# 9doFORK.net
KiCad netlist of a schematic drawn in EAGLE
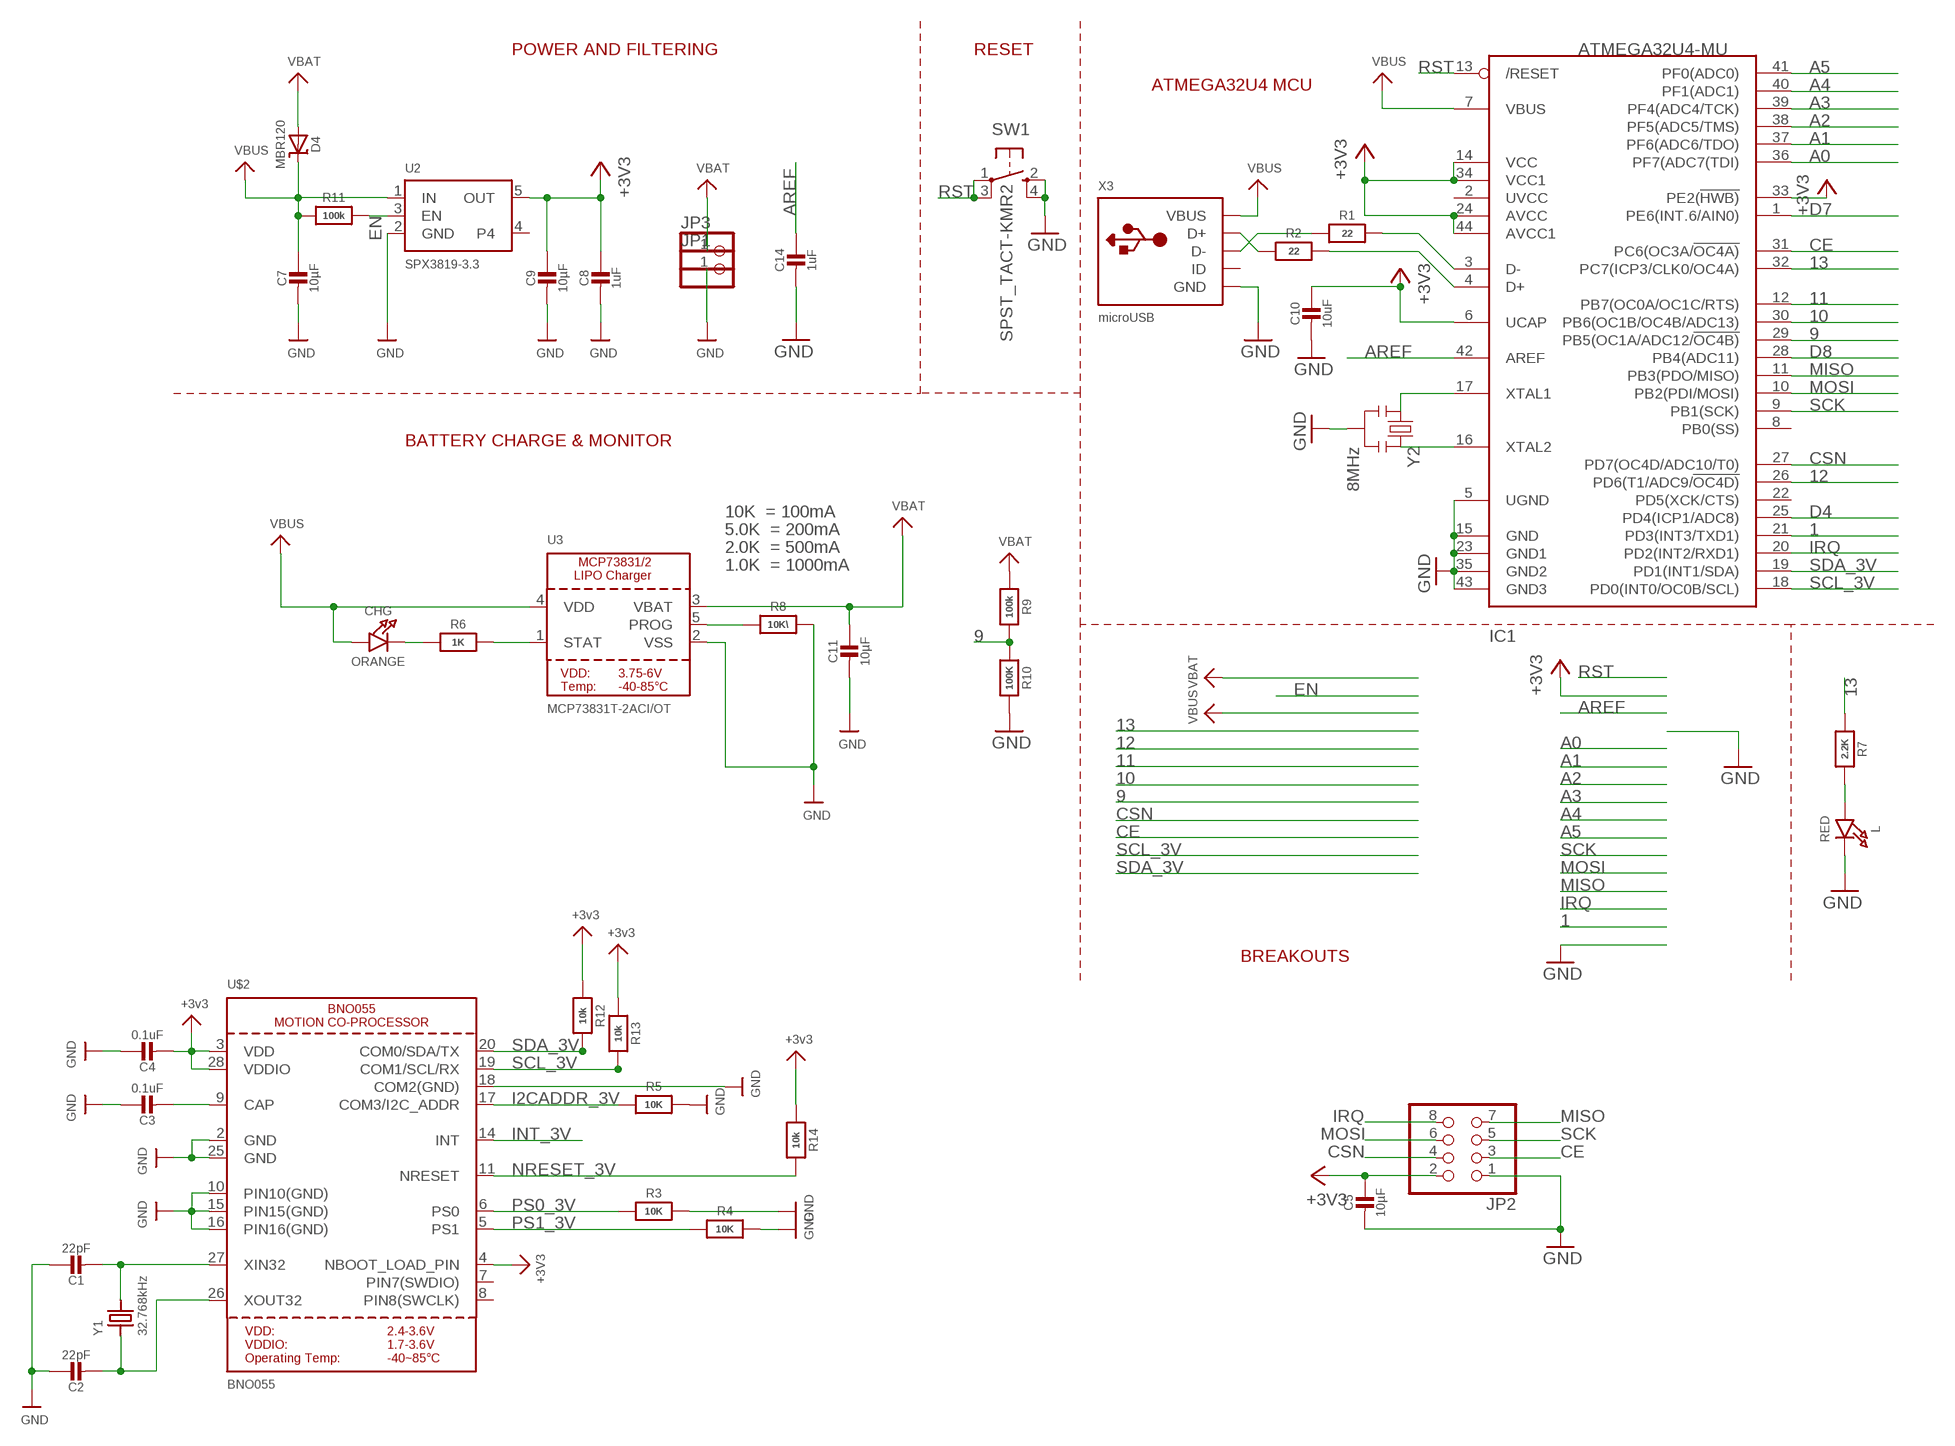
[diagram p0: schematic, sheet 1]

(export (version "E")
  (design (tool "Eeschema 10.0.6"))
  (components
    (comp (ref "C1")
      (value "22pF")
      (footprint "eagle-import:0805-NO")
      (libsource (lib "eagle-import") (part "CAP_CERAMIC0805-NOOUTLINE"))
    )
    (comp (ref "C2")
      (value "22pF")
      (footprint "eagle-import:0805-NO")
      (libsource (lib "eagle-import") (part "CAP_CERAMIC0805-NOOUTLINE"))
    )
    (comp (ref "C3")
      (value "0.1uF")
      (footprint "eagle-import:0805-NO")
      (libsource (lib "eagle-import") (part "CAP_CERAMIC0805-NOOUTLINE"))
    )
    (comp (ref "C4")
      (value "0.1uF")
      (footprint "eagle-import:0805_10MGAP")
      (libsource (lib "eagle-import") (part "CAP_CERAMIC0805_10MGAP"))
    )
    (comp (ref "C5")
      (value "10µF")
      (footprint "eagle-import:0805-NO")
      (libsource (lib "eagle-import") (part "CAP_CERAMIC0805-NOOUTLINE"))
    )
    (comp (ref "C7")
      (value "10µF")
      (footprint "eagle-import:0805-NO")
      (libsource (lib "eagle-import") (part "CAP_CERAMIC0805-NOOUTLINE"))
    )
    (comp (ref "C8")
      (value "1uF")
      (footprint "eagle-import:0603-NO")
      (libsource (lib "eagle-import") (part "CAP_CERAMIC0603_NO"))
    )
    (comp (ref "C9")
      (value "10µF")
      (footprint "eagle-import:0805-NO")
      (libsource (lib "eagle-import") (part "CAP_CERAMIC0805-NOOUTLINE"))
    )
    (comp (ref "C10")
      (value "10uF")
      (footprint "eagle-import:0805-NO")
      (libsource (lib "eagle-import") (part "CAP_CERAMIC0805-NOOUTLINE"))
    )
    (comp (ref "C11")
      (value "10µF")
      (footprint "eagle-import:0805-NO")
      (libsource (lib "eagle-import") (part "CAP_CERAMIC0805-NOOUTLINE"))
    )
    (comp (ref "C14")
      (value "1uF")
      (footprint "eagle-import:0603-NO")
      (libsource (lib "eagle-import") (part "CAP_CERAMIC0603_NO"))
    )
    (comp (ref "CHG")
      (value "ORANGE")
      (footprint "eagle-import:CHIPLED_0805_NOOUTLINE")
      (libsource (lib "eagle-import") (part "LED0805_NOOUTLINE"))
    )
    (comp (ref "D4")
      (value "MBR120")
      (footprint "eagle-import:SOD-123")
      (libsource (lib "eagle-import") (part "DIODE-SCHOTTKYSOD-123"))
    )
    (comp (ref "IC1")
      (value "ATMEGA32U4-MU")
      (footprint "eagle-import:TQFN44_7MM")
      (libsource (lib "eagle-import") (part "ATMEGA32U4-MU"))
    )
    (comp (ref "JP1")
      (value "PINHD-1X1")
      (footprint "eagle-import:1X01")
      (libsource (lib "eagle-import") (part "PINHD-1X1"))
    )
    (comp (ref "JP2")
      (value "PINHD-2X4")
      (footprint "eagle-import:2X04")
      (libsource (lib "eagle-import") (part "PINHD-2X4"))
    )
    (comp (ref "JP3")
      (value "PINHD-1X1")
      (footprint "eagle-import:1X01")
      (libsource (lib "eagle-import") (part "PINHD-1X1"))
    )
    (comp (ref "L")
      (value "RED")
      (footprint "eagle-import:CHIPLED_0805_NOOUTLINE")
      (libsource (lib "eagle-import") (part "LED0805_NOOUTLINE"))
    )
    (comp (ref "R1")
      (value "22")
      (footprint "eagle-import:0603-NO")
      (libsource (lib "eagle-import") (part "RESISTOR_0603_NOOUT"))
    )
    (comp (ref "R2")
      (value "22")
      (footprint "eagle-import:0603-NO")
      (libsource (lib "eagle-import") (part "RESISTOR_0603_NOOUT"))
    )
    (comp (ref "R3")
      (value "10K")
      (footprint "eagle-import:0805-NO")
      (libsource (lib "eagle-import") (part "RESISTOR0805_NOOUTLINE"))
    )
    (comp (ref "R4")
      (value "10K")
      (footprint "eagle-import:0805-NO")
      (libsource (lib "eagle-import") (part "RESISTOR0805_NOOUTLINE"))
    )
    (comp (ref "R5")
      (value "10K")
      (footprint "eagle-import:0805-NO")
      (libsource (lib "eagle-import") (part "RESISTOR0805_NOOUTLINE"))
    )
    (comp (ref "R6")
      (value "1K")
      (footprint "eagle-import:0603-NO")
      (libsource (lib "eagle-import") (part "RESISTOR_0603_NOOUT"))
    )
    (comp (ref "R7")
      (value "2.2K")
      (footprint "eagle-import:0603-NO")
      (libsource (lib "eagle-import") (part "RESISTOR_0603_NOOUT"))
    )
    (comp (ref "R8")
      (value "10K\\")
      (footprint "eagle-import:0603-NO")
      (libsource (lib "eagle-import") (part "RESISTOR_0603_NOOUT"))
    )
    (comp (ref "R9")
      (value "100k")
      (footprint "eagle-import:0603-NO")
      (libsource (lib "eagle-import") (part "RESISTOR_0603_NOOUT"))
    )
    (comp (ref "R10")
      (value "100K")
      (footprint "eagle-import:_0603MP")
      (libsource (lib "eagle-import") (part "RESISTOR_0603MP"))
    )
    (comp (ref "R11")
      (value "100k")
      (footprint "eagle-import:0603-NO")
      (libsource (lib "eagle-import") (part "RESISTOR_0603_NOOUT"))
    )
    (comp (ref "R12")
      (value "10k")
      (footprint "eagle-import:0603-NO")
      (libsource (lib "eagle-import") (part "RESISTOR_0603_NOOUT"))
    )
    (comp (ref "R13")
      (value "10k")
      (footprint "eagle-import:0603-NO")
      (libsource (lib "eagle-import") (part "RESISTOR_0603_NOOUT"))
    )
    (comp (ref "R14")
      (value "10k")
      (footprint "eagle-import:0603-NO")
      (libsource (lib "eagle-import") (part "RESISTOR_0603_NOOUT"))
    )
    (comp (ref "SW1")
      (value "SPST_TACT-KMR2")
      (footprint "eagle-import:KMR2")
      (libsource (lib "eagle-import") (part "SPST_TACT-KMR2"))
    )
    (comp (ref "U$2")
      (value "BNO055")
      (footprint "eagle-import:BNO055")
      (libsource (lib "eagle-import") (part "BNO055"))
    )
    (comp (ref "U2")
      (value "SPX3819-3.3")
      (footprint "eagle-import:SOT23-5")
      (libsource (lib "eagle-import") (part "VREG_SOT23-5"))
    )
    (comp (ref "U3")
      (value "MCP73831T-2ACI/OT")
      (footprint "eagle-import:SOT23-5")
      (libsource (lib "eagle-import") (part "MCP73831/2"))
    )
    (comp (ref "X3")
      (value "microUSB")
      (footprint "eagle-import:4UCONN_20329_V2")
      (libsource (lib "eagle-import") (part "USB_MICRO_20329_V2"))
    )
    (comp (ref "Y1")
      (value "32.768kHz")
      (footprint "eagle-import:CRYSTAL_8X3.8")
      (libsource (lib "eagle-import") (part "CRYSTAL8.0X3.8"))
    )
    (comp (ref "Y2")
      (value "8MHz")
      (footprint "eagle-import:RESONATOR-SMD")
      (libsource (lib "eagle-import") (part "RESONATORSMD"))
    )
  )
  (nets
    (net (code "1") (name "+3V3") (class "Default")
      (node (ref "C10") (pin "1") (pinfunction "1_1") (pintype "passive"))
      (node (ref "C4") (pin "2") (pinfunction "2_2") (pintype "passive"))
      (node (ref "C5") (pin "1") (pinfunction "1_1") (pintype "passive"))
      (node (ref "C8") (pin "1") (pinfunction "1_1") (pintype "passive"))
      (node (ref "C9") (pin "1") (pinfunction "1_1") (pintype "passive"))
      (node (ref "IC1") (pin "14") (pinfunction "VCC_14") (pintype "bidirectional"))
      (node (ref "IC1") (pin "24") (pinfunction "AVCC_24") (pintype "bidirectional"))
      (node (ref "IC1") (pin "33") (pinfunction "PE2(~{HWB})_33") (pintype "bidirectional"))
      (node (ref "IC1") (pin "34") (pinfunction "VCC1_34") (pintype "bidirectional"))
      (node (ref "IC1") (pin "44") (pinfunction "AVCC1_44") (pintype "bidirectional"))
      (node (ref "IC1") (pin "6") (pinfunction "UCAP_6") (pintype "bidirectional"))
      (node (ref "JP2") (pin "2") (pinfunction "2_2") (pintype "passive"))
      (node (ref "R12") (pin "1") (pinfunction "1_1") (pintype "passive"))
      (node (ref "R13") (pin "1") (pinfunction "1_1") (pintype "passive"))
      (node (ref "R14") (pin "1") (pinfunction "1_1") (pintype "passive"))
      (node (ref "U$2") (pin "28") (pinfunction "VDDIO_28") (pintype "power_in"))
      (node (ref "U$2") (pin "3") (pinfunction "VDD_3") (pintype "power_in"))
      (node (ref "U$2") (pin "4") (pinfunction "NBOOT_LOAD_PIN_4") (pintype "bidirectional"))
      (node (ref "U2") (pin "5") (pinfunction "OUT_5") (pintype "power_in"))
    )
    (net (code "2") (name "/1") (class "Default")
      (node (ref "IC1") (pin "21") (pinfunction "PD3(INT3/TXD1)_21") (pintype "bidirectional"))
    )
    (net (code "3") (name "/9") (class "Default")
      (node (ref "IC1") (pin "29") (pinfunction "PB5(OC1A/ADC12/~{OC4B})_29") (pintype "bidirectional"))
      (node (ref "R10") (pin "1") (pinfunction "1_1") (pintype "passive"))
      (node (ref "R9") (pin "2") (pinfunction "2_2") (pintype "passive"))
    )
    (net (code "4") (name "/10") (class "Default")
      (node (ref "IC1") (pin "30") (pinfunction "PB6(OC1B/OC4B/ADC13)_30") (pintype "bidirectional"))
    )
    (net (code "5") (name "/11") (class "Default")
      (node (ref "IC1") (pin "12") (pinfunction "PB7(OC0A/OC1C/RTS)_12") (pintype "bidirectional"))
    )
    (net (code "6") (name "/12") (class "Default")
      (node (ref "IC1") (pin "26") (pinfunction "PD6(T1/ADC9/~{OC4D})_26") (pintype "bidirectional"))
    )
    (net (code "7") (name "/13") (class "Default")
      (node (ref "IC1") (pin "32") (pinfunction "PC7(ICP3/CLK0/OC4A)_32") (pintype "bidirectional"))
      (node (ref "R7") (pin "1") (pinfunction "1_1") (pintype "passive"))
    )
    (net (code "8") (name "/A0") (class "Default")
      (node (ref "IC1") (pin "36") (pinfunction "PF7(ADC7(TDI)_36") (pintype "bidirectional"))
    )
    (net (code "9") (name "/A1") (class "Default")
      (node (ref "IC1") (pin "37") (pinfunction "PF6(ADC6/TDO)_37") (pintype "bidirectional"))
    )
    (net (code "10") (name "/A2") (class "Default")
      (node (ref "IC1") (pin "38") (pinfunction "PF5(ADC5/TMS)_38") (pintype "bidirectional"))
    )
    (net (code "11") (name "/A3") (class "Default")
      (node (ref "IC1") (pin "39") (pinfunction "PF4(ADC4/TCK)_39") (pintype "bidirectional"))
    )
    (net (code "12") (name "/A4") (class "Default")
      (node (ref "IC1") (pin "40") (pinfunction "PF1(ADC1)_40") (pintype "bidirectional"))
    )
    (net (code "13") (name "/A5") (class "Default")
      (node (ref "IC1") (pin "41") (pinfunction "PF0(ADC0)_41") (pintype "bidirectional"))
    )
    (net (code "14") (name "/AREF") (class "Default")
      (node (ref "C14") (pin "1") (pinfunction "1_1") (pintype "passive"))
      (node (ref "IC1") (pin "42") (pinfunction "AREF_42") (pintype "bidirectional"))
    )
    (net (code "15") (name "/CE") (class "Default")
      (node (ref "IC1") (pin "31") (pinfunction "PC6(OC3A/~{OC4A})_31") (pintype "bidirectional"))
      (node (ref "JP2") (pin "3") (pinfunction "3_3") (pintype "passive"))
    )
    (net (code "16") (name "/CSN") (class "Default")
      (node (ref "IC1") (pin "27") (pinfunction "PD7(OC4D/ADC10/T0)_27") (pintype "bidirectional"))
      (node (ref "JP2") (pin "4") (pinfunction "4_4") (pintype "passive"))
    )
    (net (code "17") (name "/D4") (class "Default")
      (node (ref "IC1") (pin "25") (pinfunction "PD4(ICP1/ADC8)_25") (pintype "bidirectional"))
    )
    (net (code "18") (name "/D7") (class "Default")
      (node (ref "IC1") (pin "1") (pinfunction "PE6(INT.6/AIN0)_1") (pintype "bidirectional"))
    )
    (net (code "19") (name "/D8") (class "Default")
      (node (ref "IC1") (pin "28") (pinfunction "PB4(ADC11)_28") (pintype "bidirectional"))
    )
    (net (code "20") (name "/EN") (class "Default")
      (node (ref "R11") (pin "2") (pinfunction "2_2") (pintype "passive"))
      (node (ref "U2") (pin "3") (pinfunction "EN_3") (pintype "input"))
    )
    (net (code "21") (name "/I2CADDR_3V") (class "Default")
      (node (ref "R5") (pin "1") (pinfunction "1_1") (pintype "passive"))
      (node (ref "U$2") (pin "17") (pinfunction "COM3/I2C_ADDR_17") (pintype "bidirectional"))
    )
    (net (code "22") (name "/INT_3V") (class "Default")
      (node (ref "U$2") (pin "14") (pinfunction "INT_14") (pintype "output"))
    )
    (net (code "23") (name "/IRQ") (class "Default")
      (node (ref "IC1") (pin "20") (pinfunction "PD2(INT2/RXD1)_20") (pintype "bidirectional"))
      (node (ref "JP2") (pin "8") (pinfunction "8_8") (pintype "passive"))
    )
    (net (code "24") (name "/MISO") (class "Default")
      (node (ref "IC1") (pin "11") (pinfunction "PB3(PDO/MISO)_11") (pintype "bidirectional"))
      (node (ref "JP2") (pin "7") (pinfunction "7_7") (pintype "passive"))
    )
    (net (code "25") (name "/MOSI") (class "Default")
      (node (ref "IC1") (pin "10") (pinfunction "PB2(PDI/MOSI)_10") (pintype "bidirectional"))
      (node (ref "JP2") (pin "6") (pinfunction "6_6") (pintype "passive"))
    )
    (net (code "26") (name "/NRESET_3V") (class "Default")
      (node (ref "R14") (pin "2") (pinfunction "2_2") (pintype "passive"))
      (node (ref "U$2") (pin "11") (pinfunction "NRESET_11") (pintype "bidirectional"))
    )
    (net (code "27") (name "/PS0_3V") (class "Default")
      (node (ref "R3") (pin "1") (pinfunction "1_1") (pintype "passive"))
      (node (ref "U$2") (pin "6") (pinfunction "PS0_6") (pintype "input"))
    )
    (net (code "28") (name "/PS1_3V") (class "Default")
      (node (ref "R4") (pin "1") (pinfunction "1_1") (pintype "passive"))
      (node (ref "U$2") (pin "5") (pinfunction "PS1_5") (pintype "input"))
    )
    (net (code "29") (name "/RST") (class "Default")
      (node (ref "IC1") (pin "13") (pinfunction "/RESET_13") (pintype "bidirectional"))
      (node (ref "SW1") (pin "1") (pinfunction "P_1") (pintype "passive"))
      (node (ref "SW1") (pin "3") (pinfunction "P1_3") (pintype "passive"))
    )
    (net (code "30") (name "/SCK") (class "Default")
      (node (ref "IC1") (pin "9") (pinfunction "PB1(SCK)_9") (pintype "bidirectional"))
      (node (ref "JP2") (pin "5") (pinfunction "5_5") (pintype "passive"))
    )
    (net (code "31") (name "/SCL_3V") (class "Default")
      (node (ref "IC1") (pin "18") (pinfunction "PD0(INT0/OC0B/SCL)_18") (pintype "bidirectional"))
      (node (ref "R13") (pin "2") (pinfunction "2_2") (pintype "passive"))
      (node (ref "U$2") (pin "19") (pinfunction "COM1/SCL/RX_19") (pintype "bidirectional"))
    )
    (net (code "32") (name "/SDA_3V") (class "Default")
      (node (ref "IC1") (pin "19") (pinfunction "PD1(INT1/SDA)_19") (pintype "bidirectional"))
      (node (ref "R12") (pin "2") (pinfunction "2_2") (pintype "passive"))
      (node (ref "U$2") (pin "20") (pinfunction "COM0/SDA/TX_20") (pintype "bidirectional"))
    )
    (net (code "33") (name "GND") (class "Default")
      (node (ref "C1") (pin "1") (pinfunction "1_1") (pintype "passive"))
      (node (ref "C10") (pin "2") (pinfunction "2_2") (pintype "passive"))
      (node (ref "C11") (pin "2") (pinfunction "2_2") (pintype "passive"))
      (node (ref "C14") (pin "2") (pinfunction "2_2") (pintype "passive"))
      (node (ref "C2") (pin "1") (pinfunction "1_1") (pintype "passive"))
      (node (ref "C3") (pin "1") (pinfunction "1_1") (pintype "passive"))
      (node (ref "C4") (pin "1") (pinfunction "1_1") (pintype "passive"))
      (node (ref "C5") (pin "2") (pinfunction "2_2") (pintype "passive"))
      (node (ref "C7") (pin "2") (pinfunction "2_2") (pintype "passive"))
      (node (ref "C8") (pin "2") (pinfunction "2_2") (pintype "passive"))
      (node (ref "C9") (pin "2") (pinfunction "2_2") (pintype "passive"))
      (node (ref "IC1") (pin "15") (pinfunction "GND_15") (pintype "bidirectional"))
      (node (ref "IC1") (pin "23") (pinfunction "GND1_23") (pintype "bidirectional"))
      (node (ref "IC1") (pin "35") (pinfunction "GND2_35") (pintype "bidirectional"))
      (node (ref "IC1") (pin "43") (pinfunction "GND3_43") (pintype "bidirectional"))
      (node (ref "IC1") (pin "5") (pinfunction "UGND_5") (pintype "bidirectional"))
      (node (ref "JP1") (pin "1") (pinfunction "1_1") (pintype "passive"))
      (node (ref "JP2") (pin "1") (pinfunction "1_1") (pintype "passive"))
      (node (ref "L") (pin "C") (pinfunction "C_C") (pintype "passive"))
      (node (ref "R10") (pin "2") (pinfunction "2_2") (pintype "passive"))
      (node (ref "R3") (pin "2") (pinfunction "2_2") (pintype "passive"))
      (node (ref "R4") (pin "2") (pinfunction "2_2") (pintype "passive"))
      (node (ref "R5") (pin "2") (pinfunction "2_2") (pintype "passive"))
      (node (ref "R8") (pin "2") (pinfunction "2_2") (pintype "passive"))
      (node (ref "SW1") (pin "2") (pinfunction "S_2") (pintype "passive"))
      (node (ref "SW1") (pin "4") (pinfunction "S1_4") (pintype "passive"))
      (node (ref "U$2") (pin "10") (pinfunction "PIN10(GND)_10") (pintype "bidirectional"))
      (node (ref "U$2") (pin "15") (pinfunction "PIN15(GND)_15") (pintype "bidirectional"))
      (node (ref "U$2") (pin "16") (pinfunction "PIN16(GND)_16") (pintype "bidirectional"))
      (node (ref "U$2") (pin "18") (pinfunction "COM2(GND)_18") (pintype "bidirectional"))
      (node (ref "U$2") (pin "2") (pinfunction "GND_2") (pintype "power_in"))
      (node (ref "U$2") (pin "25") (pinfunction "GND_25") (pintype "power_in"))
      (node (ref "U2") (pin "2") (pinfunction "GND_2") (pintype "power_in"))
      (node (ref "U3") (pin "2") (pinfunction "VSS_2") (pintype "power_in"))
      (node (ref "X3") (pin "BASE@1") (pinfunction "GND_BASE@1") (pintype "power_in"))
      (node (ref "X3") (pin "BASE@2") (pinfunction "GND_BASE@2") (pintype "power_in"))
      (node (ref "X3") (pin "GND") (pinfunction "GND_GND") (pintype "power_in"))
      (node (ref "X3") (pin "SPRT@1") (pinfunction "GND_SPRT@1") (pintype "power_in"))
      (node (ref "X3") (pin "SPRT@2") (pinfunction "GND_SPRT@2") (pintype "power_in"))
      (node (ref "X3") (pin "SPRT@3") (pinfunction "GND_SPRT@3") (pintype "power_in"))
      (node (ref "X3") (pin "SPRT@4") (pinfunction "GND_SPRT@4") (pintype "power_in"))
      (node (ref "Y2") (pin "2") (pinfunction "2_2") (pintype "passive"))
    )
    (net (code "34") (name "Net-(CHG-PadC)") (class "Default")
      (node (ref "CHG") (pin "C") (pinfunction "C_C") (pintype "passive"))
      (node (ref "R6") (pin "1") (pinfunction "1_1") (pintype "passive"))
    )
    (net (code "35") (name "Net-(IC1-D+)") (class "Default")
      (node (ref "IC1") (pin "4") (pinfunction "D+_4") (pintype "bidirectional"))
      (node (ref "R2") (pin "2") (pinfunction "2_2") (pintype "passive"))
    )
    (net (code "36") (name "Net-(IC1-D-)") (class "Default")
      (node (ref "IC1") (pin "3") (pinfunction "D-_3") (pintype "bidirectional"))
      (node (ref "R1") (pin "2") (pinfunction "2_2") (pintype "passive"))
    )
    (net (code "37") (name "Net-(IC1-XTAL1)") (class "Default")
      (node (ref "IC1") (pin "17") (pinfunction "XTAL1_17") (pintype "bidirectional"))
      (node (ref "Y2") (pin "1") (pinfunction "1_1") (pintype "passive"))
    )
    (net (code "38") (name "Net-(IC1-XTAL2)") (class "Default")
      (node (ref "IC1") (pin "16") (pinfunction "XTAL2_16") (pintype "bidirectional"))
      (node (ref "Y2") (pin "3") (pinfunction "3_3") (pintype "passive"))
    )
    (net (code "39") (name "Net-(L-PadA)") (class "Default")
      (node (ref "L") (pin "A") (pinfunction "A_A") (pintype "passive"))
      (node (ref "R7") (pin "2") (pinfunction "2_2") (pintype "passive"))
    )
    (net (code "40") (name "Net-(R1-Pad1)") (class "Default")
      (node (ref "R1") (pin "1") (pinfunction "1_1") (pintype "passive"))
      (node (ref "X3") (pin "D-") (pinfunction "D-_D-") (pintype "bidirectional"))
    )
    (net (code "41") (name "Net-(R2-Pad1)") (class "Default")
      (node (ref "R2") (pin "1") (pinfunction "1_1") (pintype "passive"))
      (node (ref "X3") (pin "D+") (pinfunction "D+_D+") (pintype "bidirectional"))
    )
    (net (code "42") (name "Net-(U$2-CAP)") (class "Default")
      (node (ref "C3") (pin "2") (pinfunction "2_2") (pintype "passive"))
      (node (ref "U$2") (pin "9") (pinfunction "CAP_9") (pintype "passive"))
    )
    (net (code "43") (name "Net-(U$2-XIN32)") (class "Default")
      (node (ref "C1") (pin "2") (pinfunction "2_2") (pintype "passive"))
      (node (ref "U$2") (pin "27") (pinfunction "XIN32_27") (pintype "input"))
      (node (ref "Y1") (pin "P$4") (pinfunction "2_P$4") (pintype "passive"))
    )
    (net (code "44") (name "Net-(U$2-XOUT32)") (class "Default")
      (node (ref "C2") (pin "2") (pinfunction "2_2") (pintype "passive"))
      (node (ref "U$2") (pin "26") (pinfunction "XOUT32_26") (pintype "output"))
      (node (ref "Y1") (pin "P$1") (pinfunction "1_P$1") (pintype "passive"))
    )
    (net (code "45") (name "Net-(U3-PROG)") (class "Default")
      (node (ref "R8") (pin "1") (pinfunction "1_1") (pintype "passive"))
      (node (ref "U3") (pin "5") (pinfunction "PROG_5") (pintype "input"))
    )
    (net (code "46") (name "Net-(U3-STAT)") (class "Default")
      (node (ref "R6") (pin "2") (pinfunction "2_2") (pintype "passive"))
      (node (ref "U3") (pin "1") (pinfunction "STAT_1") (pintype "output"))
    )
    (net (code "47") (name "VBAT") (class "Default")
      (node (ref "C11") (pin "1") (pinfunction "1_1") (pintype "passive"))
      (node (ref "D4") (pin "A") (pinfunction "A_A") (pintype "passive"))
      (node (ref "JP3") (pin "1") (pinfunction "1_1") (pintype "passive"))
      (node (ref "R9") (pin "1") (pinfunction "1_1") (pintype "passive"))
      (node (ref "U3") (pin "3") (pinfunction "VBAT_3") (pintype "power_in"))
    )
    (net (code "48") (name "VBUS") (class "Default")
      (node (ref "C7") (pin "1") (pinfunction "1_1") (pintype "passive"))
      (node (ref "CHG") (pin "A") (pinfunction "A_A") (pintype "passive"))
      (node (ref "D4") (pin "C") (pinfunction "C_C") (pintype "passive"))
      (node (ref "IC1") (pin "7") (pinfunction "VBUS_7") (pintype "bidirectional"))
      (node (ref "R11") (pin "1") (pinfunction "1_1") (pintype "passive"))
      (node (ref "U2") (pin "1") (pinfunction "IN_1") (pintype "power_in"))
      (node (ref "U3") (pin "4") (pinfunction "VDD_4") (pintype "power_in"))
      (node (ref "X3") (pin "VBUS") (pinfunction "VBUS_VBUS") (pintype "power_in"))
    )
    (net (code "49") (name "unconnected-(IC1-PB0(SS)-Pad8)") (class "Default")
      (node (ref "IC1") (pin "8") (pinfunction "PB0(SS)_8") (pintype "bidirectional"))
    )
    (net (code "50") (name "unconnected-(IC1-PD5(XCK{slash}CTS)-Pad22)") (class "Default")
      (node (ref "IC1") (pin "22") (pinfunction "PD5(XCK/CTS)_22") (pintype "bidirectional"))
    )
    (net (code "51") (name "unconnected-(IC1-UVCC-Pad2)") (class "Default")
      (node (ref "IC1") (pin "2") (pinfunction "UVCC_2") (pintype "bidirectional"))
    )
    (net (code "52") (name "unconnected-(U$2-PIN7(SWDIO)-Pad7)") (class "Default")
      (node (ref "U$2") (pin "7") (pinfunction "PIN7(SWDIO)_7") (pintype "bidirectional"))
    )
    (net (code "53") (name "unconnected-(U$2-PIN8(SWCLK)-Pad8)") (class "Default")
      (node (ref "U$2") (pin "8") (pinfunction "PIN8(SWCLK)_8") (pintype "bidirectional"))
    )
    (net (code "54") (name "unconnected-(U2-P4-Pad4)") (class "Default")
      (node (ref "U2") (pin "4") (pinfunction "P4_4") (pintype "bidirectional"))
    )
    (net (code "55") (name "unconnected-(X3-PadID)") (class "Default")
      (node (ref "X3") (pin "ID") (pinfunction "ID_ID") (pintype "bidirectional"))
    )
  )
)
